# tinySniff.net
KiCad netlist of a schematic drawn in Altium Designer
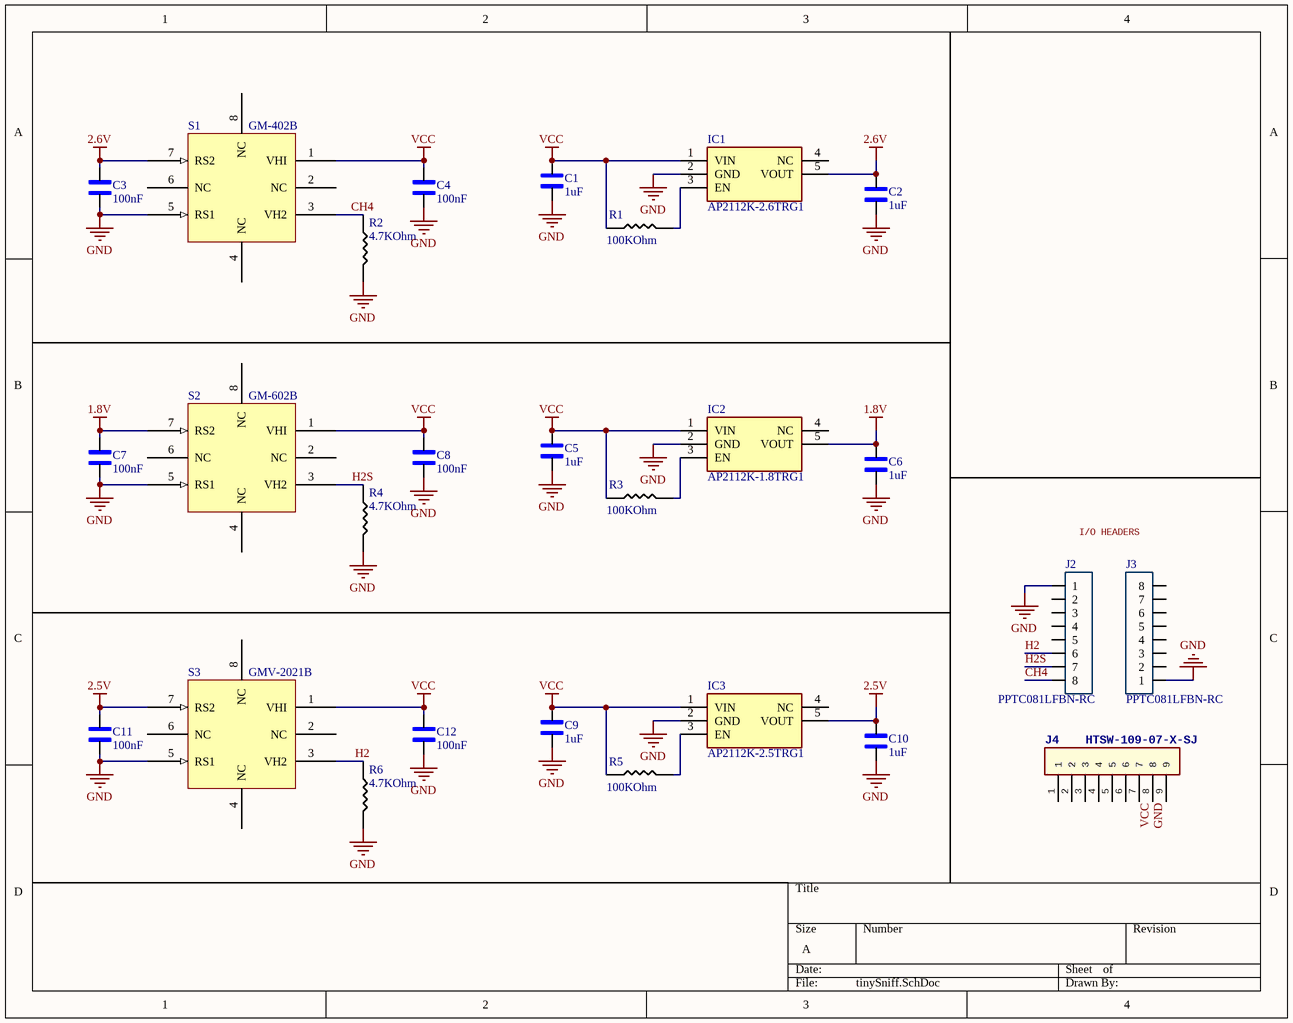
[diagram p0: tinySniff.SchDoc]

(export (version "E")
  (design (tool "Eeschema 10.0.6"))
  (components
    (comp (ref "C1")
      (value "1uF")
      (footprint "1206_Passive_Capacitor")
      (description "MULTILAYER CERAMIC CAPACITORS MLCC - SMD/SMT 1UF 50V 1206 ROHS")
      (fields (field (name "MFR PART #") "CL31B105KBHNNNE") (field (name "LCSC PART#") "C1848"))
      (libsource (lib "ECEN5730Lib_2023_05_DS (2)") (part "C_1uF_1206"))
    )
    (comp (ref "C2")
      (value "1uF")
      (footprint "1206_Passive_Capacitor")
      (description "MULTILAYER CERAMIC CAPACITORS MLCC - SMD/SMT 1UF 50V 1206 ROHS")
      (fields (field (name "MFR PART #") "CL31B105KBHNNNE") (field (name "LCSC PART#") "C1848"))
      (libsource (lib "ECEN5730Lib_2023_05_DS (2)") (part "C_1uF_1206"))
    )
    (comp (ref "C3")
      (value "100nF")
      (footprint "1206_Passive_Capacitor")
      (description "100nF ±5% 50V C0G 1206 Multilayer Ceramic Capacitors MLCC - SMD/SMT RoHS")
      (fields (field (name "LCSC PART#") "C21812") (field (name "MFR PART #") "GRM31M5C1H473JA01L"))
      (libsource (lib "ECEN5730Lib_2023_05_DS (2)") (part "C_47nF_1206"))
    )
    (comp (ref "C4")
      (value "100nF")
      (footprint "1206_Passive_Capacitor")
      (description "100nF ±5% 50V C0G 1206 Multilayer Ceramic Capacitors MLCC - SMD/SMT RoHS")
      (fields (field (name "LCSC PART#") "C21812") (field (name "MFR PART #") "GRM31M5C1H473JA01L"))
      (libsource (lib "ECEN5730Lib_2023_05_DS (2)") (part "C_47nF_1206"))
    )
    (comp (ref "C5")
      (value "1uF")
      (footprint "1206_Passive_Capacitor")
      (description "MULTILAYER CERAMIC CAPACITORS MLCC - SMD/SMT 1UF 50V 1206 ROHS")
      (fields (field (name "MFR PART #") "CL31B105KBHNNNE") (field (name "LCSC PART#") "C1848"))
      (libsource (lib "ECEN5730Lib_2023_05_DS (2)") (part "C_1uF_1206"))
    )
    (comp (ref "C6")
      (value "1uF")
      (footprint "1206_Passive_Capacitor")
      (description "MULTILAYER CERAMIC CAPACITORS MLCC - SMD/SMT 1UF 50V 1206 ROHS")
      (fields (field (name "MFR PART #") "CL31B105KBHNNNE") (field (name "LCSC PART#") "C1848"))
      (libsource (lib "ECEN5730Lib_2023_05_DS (2)") (part "C_1uF_1206"))
    )
    (comp (ref "C7")
      (value "100nF")
      (footprint "1206_Passive_Capacitor")
      (description "100nF ±5% 50V C0G 1206 Multilayer Ceramic Capacitors MLCC - SMD/SMT RoHS")
      (fields (field (name "LCSC PART#") "C21812") (field (name "MFR PART #") "GRM31M5C1H473JA01L"))
      (libsource (lib "ECEN5730Lib_2023_05_DS (2)") (part "C_47nF_1206"))
    )
    (comp (ref "C8")
      (value "100nF")
      (footprint "1206_Passive_Capacitor")
      (description "100nF ±5% 50V C0G 1206 Multilayer Ceramic Capacitors MLCC - SMD/SMT RoHS")
      (fields (field (name "LCSC PART#") "C21812") (field (name "MFR PART #") "GRM31M5C1H473JA01L"))
      (libsource (lib "ECEN5730Lib_2023_05_DS (2)") (part "C_47nF_1206"))
    )
    (comp (ref "C9")
      (value "1uF")
      (footprint "1206_Passive_Capacitor")
      (description "MULTILAYER CERAMIC CAPACITORS MLCC - SMD/SMT 1UF 50V 1206 ROHS")
      (fields (field (name "MFR PART #") "CL31B105KBHNNNE") (field (name "LCSC PART#") "C1848"))
      (libsource (lib "ECEN5730Lib_2023_05_DS (2)") (part "C_1uF_1206"))
    )
    (comp (ref "C10")
      (value "1uF")
      (footprint "1206_Passive_Capacitor")
      (description "MULTILAYER CERAMIC CAPACITORS MLCC - SMD/SMT 1UF 50V 1206 ROHS")
      (fields (field (name "MFR PART #") "CL31B105KBHNNNE") (field (name "LCSC PART#") "C1848"))
      (libsource (lib "ECEN5730Lib_2023_05_DS (2)") (part "C_1uF_1206"))
    )
    (comp (ref "C11")
      (value "100nF")
      (footprint "1206_Passive_Capacitor")
      (description "100nF ±5% 50V C0G 1206 Multilayer Ceramic Capacitors MLCC - SMD/SMT RoHS")
      (fields (field (name "LCSC PART#") "C21812") (field (name "MFR PART #") "GRM31M5C1H473JA01L"))
      (libsource (lib "ECEN5730Lib_2023_05_DS (2)") (part "C_47nF_1206"))
    )
    (comp (ref "C12")
      (value "100nF")
      (footprint "1206_Passive_Capacitor")
      (description "100nF ±5% 50V C0G 1206 Multilayer Ceramic Capacitors MLCC - SMD/SMT RoHS")
      (fields (field (name "LCSC PART#") "C21812") (field (name "MFR PART #") "GRM31M5C1H473JA01L"))
      (libsource (lib "ECEN5730Lib_2023_05_DS (2)") (part "C_47nF_1206"))
    )
    (comp (ref "IC1")
      (value "AP2112K-2.6TRG1")
      (footprint "SOT95P285X140-5N")
      (description "600mA 1.8V LDO Regulator Enable SOT23-5")
      (fields
        (field (name "ARROW PART NUMBER") "AP2112K-1.8TRG1")
        (field (name "MOUSER PART NUMBER") "621-AP2112K-1.8TRG1")
      )
      (libsource (lib "McIntyre Industries") (part "AP2112K-1.8TRG1"))
    )
    (comp (ref "IC2")
      (value "AP2112K-1.8TRG1")
      (footprint "SOT95P285X140-5N")
      (description "600mA 1.8V LDO Regulator Enable SOT23-5")
      (fields (field (name "MOUSER PART NUMBER") "621-AP2112K-1.8TRG1"))
      (libsource (lib "McIntyre Industries") (part "AP2112K-1.8TRG1"))
    )
    (comp (ref "IC3")
      (value "AP2112K-2.5TRG1")
      (footprint "SOT95P285X140-5N")
      (description "600mA 1.8V LDO Regulator Enable SOT23-5")
      (fields
        (field (name "ARROW PART NUMBER") "AP2112K-1.8TRG1")
        (field (name "MOUSER PART NUMBER") "621-AP2112K-1.8TRG1")
      )
      (libsource (lib "McIntyre Industries") (part "AP2112K-1.8TRG1"))
    )
    (comp (ref "J2")
      (value "PPTC081LFBN-RC")
      (footprint "8_PIN_100MIL - Female")
      (description "8 Position Header Connector 0.100\" (2.54mm) Through Hole Tin")
      (fields (field (name "LCSC PART#") "C27438"))
      (libsource (lib "ECEN5730Lib_2023_05_DS (2)") (part "JF_8_PIN_FEMALE"))
    )
    (comp (ref "J3")
      (value "PPTC081LFBN-RC")
      (footprint "8_PIN_100MIL - Female")
      (description "8 Position Header Connector 0.100\" (2.54mm) Through Hole Tin")
      (fields (field (name "LCSC PART#") "C27438"))
      (libsource (lib "") (part "JF_8_PIN_FEMALE_1"))
    )
    (comp (ref "J4")
      (value "HTSW-109-07-X-SJ")
      (footprint "JM-9_HTSW-109-07-X-S")
      (description "2.54mm Black 1x9P Straight,P=2.54mm Pin Headers")
      (fields (field (name "MFR PART #") "PZ254-1-09-Z-8.5") (field (name "LCSC PART#") "C2894932"))
      (libsource (lib "ECEN5730Lib_2023_05_DS (2)") (part "JM_9_PIN_MALE"))
    )
    (comp (ref "R1")
      (value "100KOhm")
      (footprint "1206_Passive_Resitor")
      (description "100kΩ ±1% 0.25W ±100ppm/℃ 1206 Chip Resistor - Surface Mount RoHS")
      (fields (field (name "LCSC PART#") "C17900") (field (name "MFR PART #") "1206W4F1003T5E"))
      (libsource (lib "ECEN5730Lib_2023_05_DS (2)") (part "R_100KOhm_1206"))
    )
    (comp (ref "R2")
      (value "4.7KOhm")
      (footprint "1206_Passive_Resitor")
      (description "4.7kΩ ±1% 0.25W ±100ppm/℃ 1206 Chip Resistor - Surface Mount RoHS")
      (fields (field (name "LCSC PART#") "C17936") (field (name "MFR PART #") "1206W4F4701T5E"))
      (libsource (lib "ECEN5730Lib_2023_05_DS (2)") (part "R_4.7k_1206"))
    )
    (comp (ref "R3")
      (value "100KOhm")
      (footprint "1206_Passive_Resitor")
      (description "100kΩ ±1% 0.25W ±100ppm/℃ 1206 Chip Resistor - Surface Mount RoHS")
      (fields (field (name "LCSC PART#") "C17900") (field (name "MFR PART #") "1206W4F1003T5E"))
      (libsource (lib "ECEN5730Lib_2023_05_DS (2)") (part "R_100KOhm_1206"))
    )
    (comp (ref "R4")
      (value "4.7KOhm")
      (footprint "1206_Passive_Resitor")
      (description "4.7kΩ ±1% 0.25W ±100ppm/℃ 1206 Chip Resistor - Surface Mount RoHS")
      (fields (field (name "LCSC PART#") "C17936") (field (name "MFR PART #") "1206W4F4701T5E"))
      (libsource (lib "ECEN5730Lib_2023_05_DS (2)") (part "R_4.7k_1206"))
    )
    (comp (ref "R5")
      (value "100KOhm")
      (footprint "1206_Passive_Resitor")
      (description "100kΩ ±1% 0.25W ±100ppm/℃ 1206 Chip Resistor - Surface Mount RoHS")
      (fields (field (name "LCSC PART#") "C17900") (field (name "MFR PART #") "1206W4F1003T5E"))
      (libsource (lib "ECEN5730Lib_2023_05_DS (2)") (part "R_100KOhm_1206"))
    )
    (comp (ref "R6")
      (value "4.7KOhm")
      (footprint "1206_Passive_Resitor")
      (description "4.7kΩ ±1% 0.25W ±100ppm/℃ 1206 Chip Resistor - Surface Mount RoHS")
      (fields (field (name "LCSC PART#") "C17936") (field (name "MFR PART #") "1206W4F4701T5E"))
      (libsource (lib "ECEN5730Lib_2023_05_DS (2)") (part "R_4.7k_1206"))
    )
    (comp (ref "S1")
      (value "GM-402B")
      (footprint "QFN127P500X500X155_HS-9N")
      (description "Generic MEMS footprint for GM series devices from Winsen")
      (libsource (lib "McIntyre Industries") (part "New symbol 1"))
    )
    (comp (ref "S2")
      (value "GM-602B")
      (footprint "QFN127P500X500X155_HS-9N")
      (description "Generic MEMS footprint for GM series devices from Winsen")
      (libsource (lib "McIntyre Industries") (part "New symbol 1"))
    )
    (comp (ref "S3")
      (value "GMV-2021B")
      (footprint "QFN127P500X500X155_HS-9N")
      (description "Generic MEMS footprint for GM series devices from Winsen")
      (libsource (lib "McIntyre Industries") (part "New symbol 1"))
    )
  )
  (nets
    (net (code "1") (name "/CH4") (class "Default")
      (node (ref "J2") (pin "8") (pinfunction "8_8") (pintype "passive"))
      (node (ref "R2") (pin "1") (pinfunction "1_1") (pintype "passive"))
      (node (ref "S1") (pin "3") (pinfunction "VH2_3") (pintype "power_in"))
    )
    (net (code "2") (name "/H2") (class "Default")
      (node (ref "J2") (pin "6") (pinfunction "6_6") (pintype "passive"))
      (node (ref "R6") (pin "1") (pinfunction "1_1") (pintype "passive"))
      (node (ref "S3") (pin "3") (pinfunction "VH2_3") (pintype "power_in"))
    )
    (net (code "3") (name "/H2S") (class "Default")
      (node (ref "J2") (pin "7") (pinfunction "7_7") (pintype "passive"))
      (node (ref "R4") (pin "1") (pinfunction "1_1") (pintype "passive"))
      (node (ref "S2") (pin "3") (pinfunction "VH2_3") (pintype "power_in"))
    )
    (net (code "4") (name "1.8V") (class "Default")
      (node (ref "C6") (pin "2") (pinfunction "2_2") (pintype "passive"))
      (node (ref "C7") (pin "2") (pinfunction "2_2") (pintype "passive"))
      (node (ref "IC2") (pin "5") (pinfunction "VOUT_5") (pintype "passive"))
      (node (ref "S2") (pin "7") (pinfunction "RS2_7") (pintype "input"))
    )
    (net (code "5") (name "2.5V") (class "Default")
      (node (ref "C10") (pin "2") (pinfunction "2_2") (pintype "passive"))
      (node (ref "C11") (pin "2") (pinfunction "2_2") (pintype "passive"))
      (node (ref "IC3") (pin "5") (pinfunction "VOUT_5") (pintype "passive"))
      (node (ref "S3") (pin "7") (pinfunction "RS2_7") (pintype "input"))
    )
    (net (code "6") (name "2.6V") (class "Default")
      (node (ref "C2") (pin "2") (pinfunction "2_2") (pintype "passive"))
      (node (ref "C3") (pin "2") (pinfunction "2_2") (pintype "passive"))
      (node (ref "IC1") (pin "5") (pinfunction "VOUT_5") (pintype "passive"))
      (node (ref "S1") (pin "7") (pinfunction "RS2_7") (pintype "input"))
    )
    (net (code "7") (name "GND") (class "Default")
      (node (ref "C1") (pin "1") (pinfunction "1_1") (pintype "passive"))
      (node (ref "C10") (pin "1") (pinfunction "1_1") (pintype "passive"))
      (node (ref "C11") (pin "1") (pinfunction "1_1") (pintype "passive"))
      (node (ref "C12") (pin "2") (pinfunction "2_2") (pintype "passive"))
      (node (ref "C2") (pin "1") (pinfunction "1_1") (pintype "passive"))
      (node (ref "C3") (pin "1") (pinfunction "1_1") (pintype "passive"))
      (node (ref "C4") (pin "2") (pinfunction "2_2") (pintype "passive"))
      (node (ref "C5") (pin "1") (pinfunction "1_1") (pintype "passive"))
      (node (ref "C6") (pin "1") (pinfunction "1_1") (pintype "passive"))
      (node (ref "C7") (pin "1") (pinfunction "1_1") (pintype "passive"))
      (node (ref "C8") (pin "2") (pinfunction "2_2") (pintype "passive"))
      (node (ref "C9") (pin "1") (pinfunction "1_1") (pintype "passive"))
      (node (ref "IC1") (pin "2") (pinfunction "GND_2") (pintype "passive"))
      (node (ref "IC2") (pin "2") (pinfunction "GND_2") (pintype "passive"))
      (node (ref "IC3") (pin "2") (pinfunction "GND_2") (pintype "passive"))
      (node (ref "J2") (pin "1") (pinfunction "1_1") (pintype "passive"))
      (node (ref "J3") (pin "1") (pinfunction "1_1") (pintype "passive"))
      (node (ref "J4") (pin "9") (pinfunction "9_9") (pintype "passive"))
      (node (ref "R2") (pin "2") (pinfunction "2_2") (pintype "passive"))
      (node (ref "R4") (pin "2") (pinfunction "2_2") (pintype "passive"))
      (node (ref "R6") (pin "2") (pinfunction "2_2") (pintype "passive"))
      (node (ref "S1") (pin "5") (pinfunction "RS1_5") (pintype "input"))
      (node (ref "S2") (pin "5") (pinfunction "RS1_5") (pintype "input"))
      (node (ref "S3") (pin "5") (pinfunction "RS1_5") (pintype "input"))
    )
    (net (code "8") (name "Net-(IC1-EN)") (class "Default")
      (node (ref "IC1") (pin "3") (pinfunction "EN_3") (pintype "passive"))
      (node (ref "R1") (pin "2") (pinfunction "2_2") (pintype "passive"))
    )
    (net (code "9") (name "Net-(IC2-EN)") (class "Default")
      (node (ref "IC2") (pin "3") (pinfunction "EN_3") (pintype "passive"))
      (node (ref "R3") (pin "2") (pinfunction "2_2") (pintype "passive"))
    )
    (net (code "10") (name "Net-(IC3-EN)") (class "Default")
      (node (ref "IC3") (pin "3") (pinfunction "EN_3") (pintype "passive"))
      (node (ref "R5") (pin "2") (pinfunction "2_2") (pintype "passive"))
    )
    (net (code "11") (name "VCC") (class "Default")
      (node (ref "C1") (pin "2") (pinfunction "2_2") (pintype "passive"))
      (node (ref "C12") (pin "1") (pinfunction "1_1") (pintype "passive"))
      (node (ref "C4") (pin "1") (pinfunction "1_1") (pintype "passive"))
      (node (ref "C5") (pin "2") (pinfunction "2_2") (pintype "passive"))
      (node (ref "C8") (pin "1") (pinfunction "1_1") (pintype "passive"))
      (node (ref "C9") (pin "2") (pinfunction "2_2") (pintype "passive"))
      (node (ref "IC1") (pin "1") (pinfunction "VIN_1") (pintype "passive"))
      (node (ref "IC2") (pin "1") (pinfunction "VIN_1") (pintype "passive"))
      (node (ref "IC3") (pin "1") (pinfunction "VIN_1") (pintype "passive"))
      (node (ref "J4") (pin "8") (pinfunction "8_8") (pintype "passive"))
      (node (ref "R1") (pin "1") (pinfunction "1_1") (pintype "passive"))
      (node (ref "R3") (pin "1") (pinfunction "1_1") (pintype "passive"))
      (node (ref "R5") (pin "1") (pinfunction "1_1") (pintype "passive"))
      (node (ref "S1") (pin "1") (pinfunction "VHI_1") (pintype "power_in"))
      (node (ref "S2") (pin "1") (pinfunction "VHI_1") (pintype "power_in"))
      (node (ref "S3") (pin "1") (pinfunction "VHI_1") (pintype "power_in"))
    )
    (net (code "12") (name "unconnected-(IC1-NC-Pad4)") (class "Default")
      (node (ref "IC1") (pin "4") (pinfunction "NC_4") (pintype "passive"))
    )
    (net (code "13") (name "unconnected-(IC2-NC-Pad4)") (class "Default")
      (node (ref "IC2") (pin "4") (pinfunction "NC_4") (pintype "passive"))
    )
    (net (code "14") (name "unconnected-(IC3-NC-Pad4)") (class "Default")
      (node (ref "IC3") (pin "4") (pinfunction "NC_4") (pintype "passive"))
    )
    (net (code "15") (name "unconnected-(J2-Pad2)") (class "Default")
      (node (ref "J2") (pin "2") (pinfunction "2_2") (pintype "passive"))
    )
    (net (code "16") (name "unconnected-(J2-Pad3)") (class "Default")
      (node (ref "J2") (pin "3") (pinfunction "3_3") (pintype "passive"))
    )
    (net (code "17") (name "unconnected-(J2-Pad4)") (class "Default")
      (node (ref "J2") (pin "4") (pinfunction "4_4") (pintype "passive"))
    )
    (net (code "18") (name "unconnected-(J2-Pad5)") (class "Default")
      (node (ref "J2") (pin "5") (pinfunction "5_5") (pintype "passive"))
    )
    (net (code "19") (name "unconnected-(J3-Pad2)") (class "Default")
      (node (ref "J3") (pin "2") (pinfunction "2_2") (pintype "passive"))
    )
    (net (code "20") (name "unconnected-(J3-Pad3)") (class "Default")
      (node (ref "J3") (pin "3") (pinfunction "3_3") (pintype "passive"))
    )
    (net (code "21") (name "unconnected-(J3-Pad4)") (class "Default")
      (node (ref "J3") (pin "4") (pinfunction "4_4") (pintype "passive"))
    )
    (net (code "22") (name "unconnected-(J3-Pad5)") (class "Default")
      (node (ref "J3") (pin "5") (pinfunction "5_5") (pintype "passive"))
    )
    (net (code "23") (name "unconnected-(J3-Pad6)") (class "Default")
      (node (ref "J3") (pin "6") (pinfunction "6_6") (pintype "passive"))
    )
    (net (code "24") (name "unconnected-(J3-Pad7)") (class "Default")
      (node (ref "J3") (pin "7") (pinfunction "7_7") (pintype "passive"))
    )
    (net (code "25") (name "unconnected-(J3-Pad8)") (class "Default")
      (node (ref "J3") (pin "8") (pinfunction "8_8") (pintype "passive"))
    )
    (net (code "26") (name "unconnected-(J4-Pad1)") (class "Default")
      (node (ref "J4") (pin "1") (pinfunction "1_1") (pintype "passive"))
    )
    (net (code "27") (name "unconnected-(J4-Pad2)") (class "Default")
      (node (ref "J4") (pin "2") (pinfunction "2_2") (pintype "passive"))
    )
    (net (code "28") (name "unconnected-(J4-Pad3)") (class "Default")
      (node (ref "J4") (pin "3") (pinfunction "3_3") (pintype "passive"))
    )
    (net (code "29") (name "unconnected-(J4-Pad4)") (class "Default")
      (node (ref "J4") (pin "4") (pinfunction "4_4") (pintype "passive"))
    )
    (net (code "30") (name "unconnected-(J4-Pad5)") (class "Default")
      (node (ref "J4") (pin "5") (pinfunction "5_5") (pintype "passive"))
    )
    (net (code "31") (name "unconnected-(J4-Pad6)") (class "Default")
      (node (ref "J4") (pin "6") (pinfunction "6_6") (pintype "passive"))
    )
    (net (code "32") (name "unconnected-(J4-Pad7)") (class "Default")
      (node (ref "J4") (pin "7") (pinfunction "7_7") (pintype "passive"))
    )
    (net (code "33") (name "unconnected-(S1-NC-Pad2)") (class "Default")
      (node (ref "S1") (pin "2") (pinfunction "NC_2") (pintype "passive"))
    )
    (net (code "34") (name "unconnected-(S1-NC-Pad4)") (class "Default")
      (node (ref "S1") (pin "4") (pinfunction "NC_4") (pintype "passive"))
    )
    (net (code "35") (name "unconnected-(S1-NC-Pad6)") (class "Default")
      (node (ref "S1") (pin "6") (pinfunction "NC_6") (pintype "passive"))
    )
    (net (code "36") (name "unconnected-(S1-NC-Pad8)") (class "Default")
      (node (ref "S1") (pin "8") (pinfunction "NC_8") (pintype "passive"))
    )
    (net (code "37") (name "unconnected-(S2-NC-Pad2)") (class "Default")
      (node (ref "S2") (pin "2") (pinfunction "NC_2") (pintype "passive"))
    )
    (net (code "38") (name "unconnected-(S2-NC-Pad4)") (class "Default")
      (node (ref "S2") (pin "4") (pinfunction "NC_4") (pintype "passive"))
    )
    (net (code "39") (name "unconnected-(S2-NC-Pad6)") (class "Default")
      (node (ref "S2") (pin "6") (pinfunction "NC_6") (pintype "passive"))
    )
    (net (code "40") (name "unconnected-(S2-NC-Pad8)") (class "Default")
      (node (ref "S2") (pin "8") (pinfunction "NC_8") (pintype "passive"))
    )
    (net (code "41") (name "unconnected-(S3-NC-Pad2)") (class "Default")
      (node (ref "S3") (pin "2") (pinfunction "NC_2") (pintype "passive"))
    )
    (net (code "42") (name "unconnected-(S3-NC-Pad4)") (class "Default")
      (node (ref "S3") (pin "4") (pinfunction "NC_4") (pintype "passive"))
    )
    (net (code "43") (name "unconnected-(S3-NC-Pad6)") (class "Default")
      (node (ref "S3") (pin "6") (pinfunction "NC_6") (pintype "passive"))
    )
    (net (code "44") (name "unconnected-(S3-NC-Pad8)") (class "Default")
      (node (ref "S3") (pin "8") (pinfunction "NC_8") (pintype "passive"))
    )
  )
)
